# OX05B1S_CAM0.net
KiCad netlist of a schematic drawn in Altium Designer
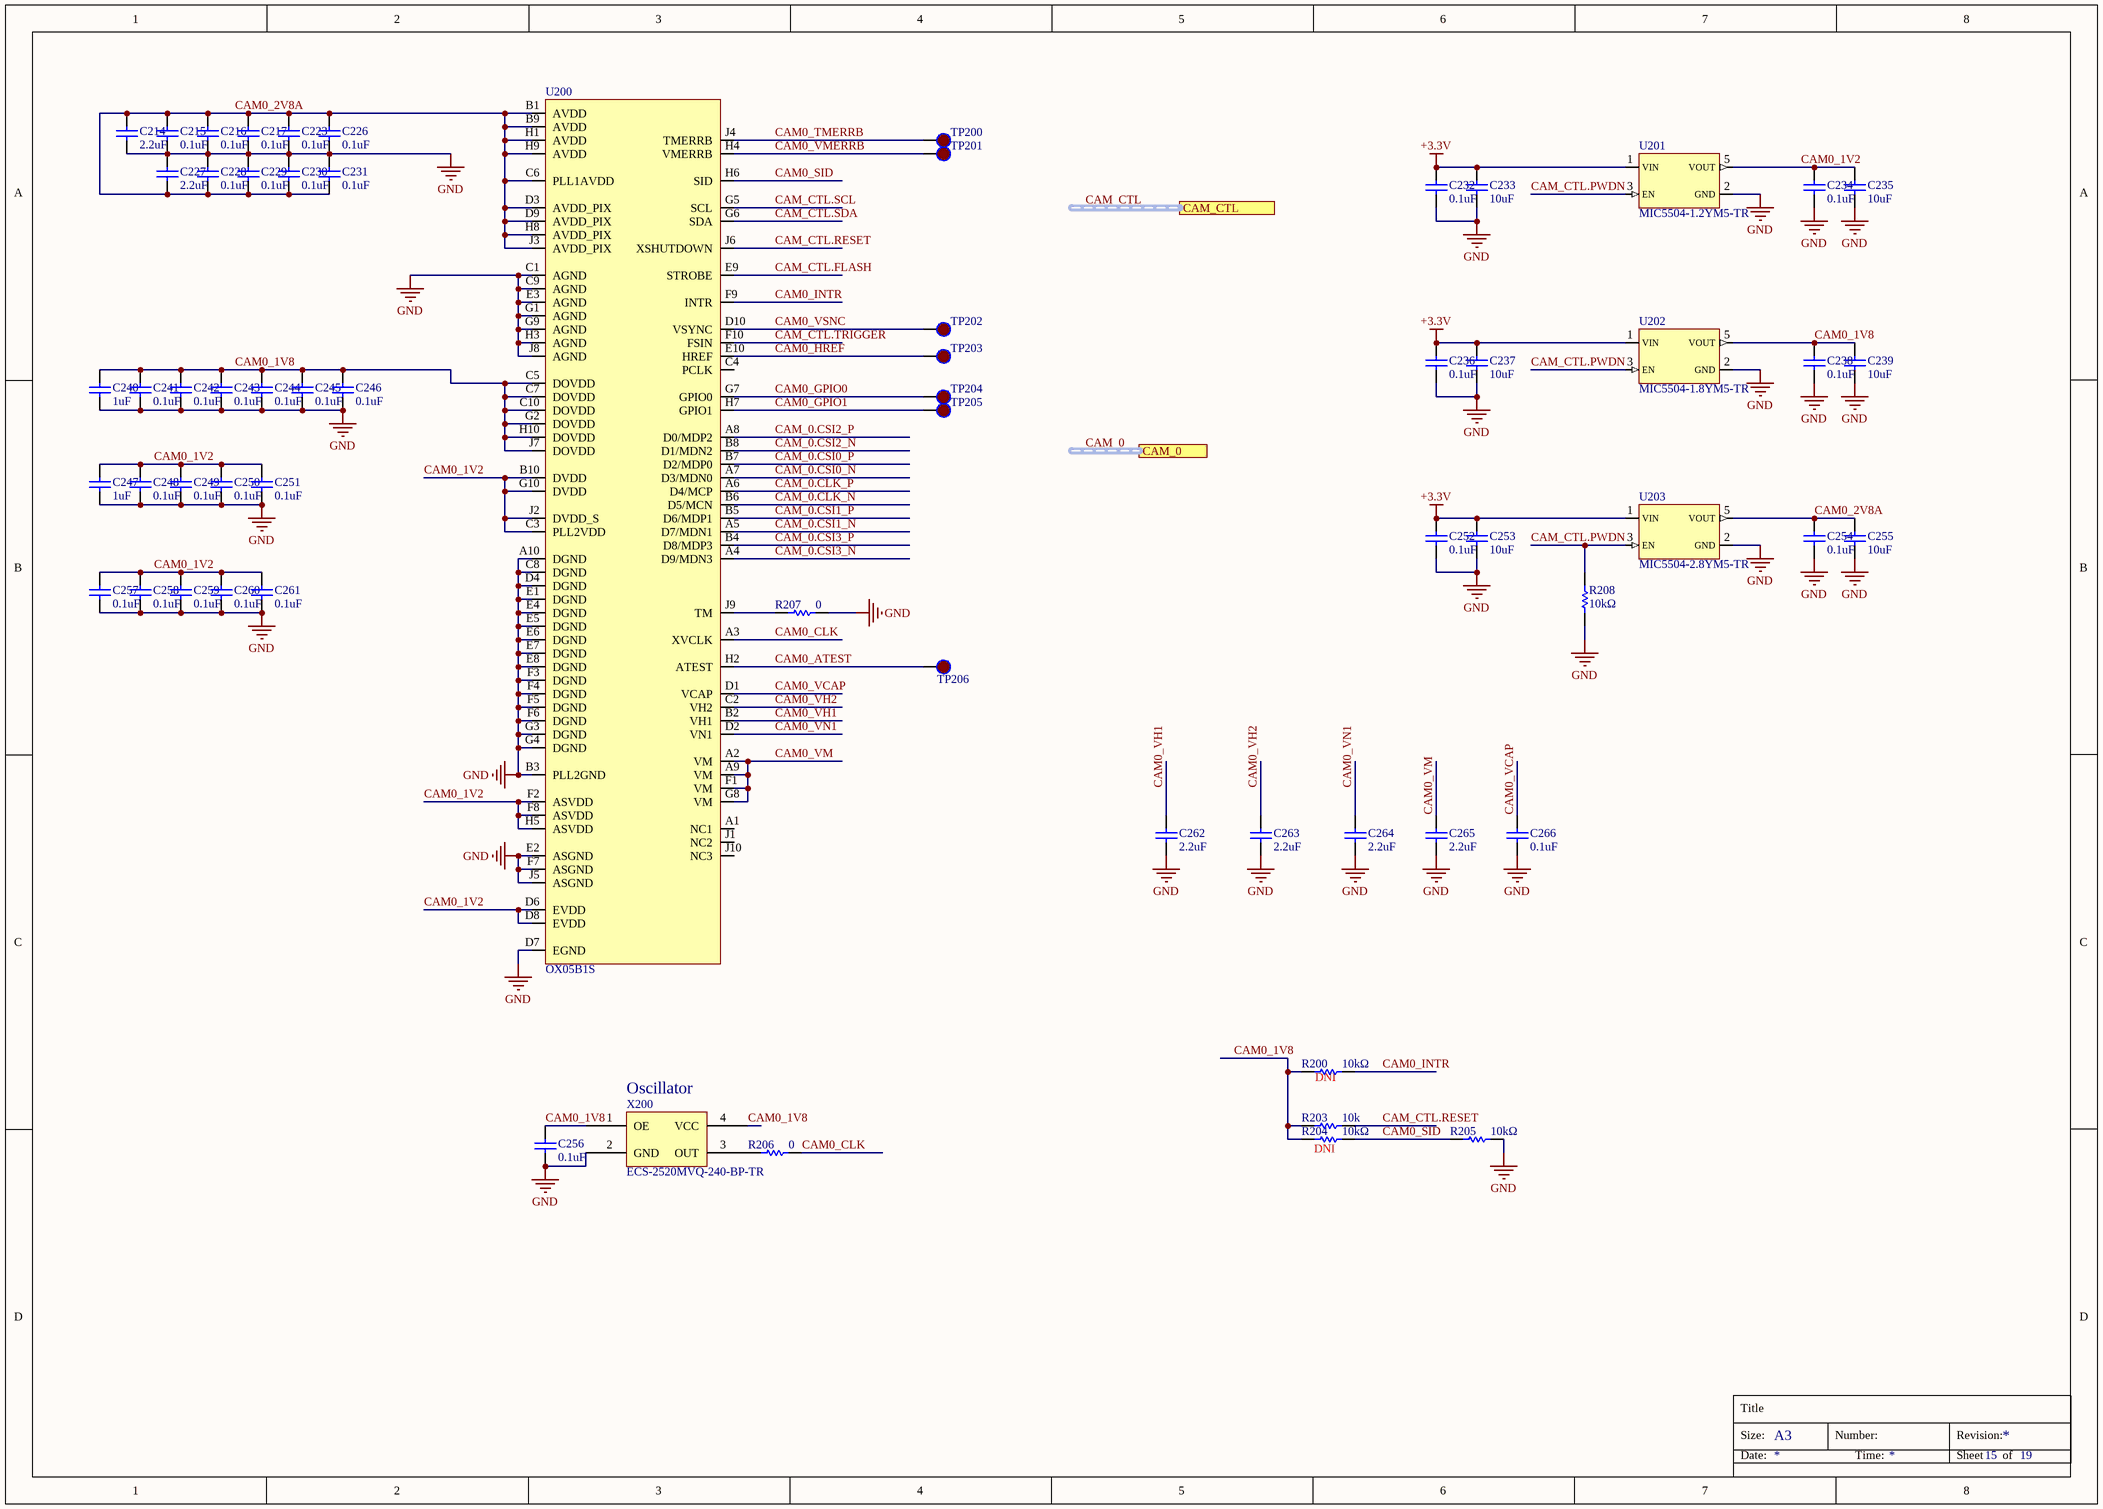
[diagram p0: OX05B1S_CAM0.SchDoc]

(export (version "E")
  (design (tool "Eeschema 10.0.6"))
  (components
    (comp (ref "C214")
      (value "2.2uF")
      (footprint "Signetik-passives:0402_CAP_NP")
      (description "CAP CER 2.2UF 6.3V X5R ±10% 0402")
      (fields
        (field (name "MANUFACTURER") "Murata")
        (field (name "MANUFACTURER PART NUMBER") "GRM155R60J225KE95D")
      )
      (libsource (lib "Signetik-passives") (part "0402C_2.2UF_6.3V_10%_X5R"))
    )
    (comp (ref "C215")
      (value "0.1uF")
      (footprint "signetik-passives:0402_CAP_NP")
      (description "CAP CER 0.1UF 25V X7R 0402")
      (fields (field (name "MANUFACTURER") "AVX") (field (name "MANUFACTURER PART NUMBER") "04023C104KAT2A"))
      (libsource (lib "Signetik-passives") (part "0402C_0.1UF_25V_10%_X7R"))
    )
    (comp (ref "C216")
      (value "0.1uF")
      (footprint "signetik-passives:0402_CAP_NP")
      (description "CAP CER 0.1UF 25V X7R 0402")
      (fields (field (name "MANUFACTURER") "AVX") (field (name "MANUFACTURER PART NUMBER") "04023C104KAT2A"))
      (libsource (lib "Signetik-passives") (part "0402C_0.1UF_25V_10%_X7R"))
    )
    (comp (ref "C217")
      (value "0.1uF")
      (footprint "signetik-passives:0402_CAP_NP")
      (description "CAP CER 0.1UF 25V X7R 0402")
      (fields (field (name "MANUFACTURER") "AVX") (field (name "MANUFACTURER PART NUMBER") "04023C104KAT2A"))
      (libsource (lib "Signetik-passives") (part "0402C_0.1UF_25V_10%_X7R"))
    )
    (comp (ref "C223")
      (value "0.1uF")
      (footprint "signetik-passives:0402_CAP_NP")
      (description "CAP CER 0.1UF 25V X7R 0402")
      (fields (field (name "MANUFACTURER") "AVX") (field (name "MANUFACTURER PART NUMBER") "04023C104KAT2A"))
      (libsource (lib "Signetik-passives") (part "0402C_0.1UF_25V_10%_X7R"))
    )
    (comp (ref "C226")
      (value "0.1uF")
      (footprint "signetik-passives:0402_CAP_NP")
      (description "CAP CER 0.1UF 25V X7R 0402")
      (fields (field (name "MANUFACTURER") "AVX") (field (name "MANUFACTURER PART NUMBER") "04023C104KAT2A"))
      (libsource (lib "Signetik-passives") (part "0402C_0.1UF_25V_10%_X7R"))
    )
    (comp (ref "C227")
      (value "2.2uF")
      (footprint "Signetik-passives:0402_CAP_NP")
      (description "CAP CER 2.2UF 6.3V X5R ±10% 0402")
      (fields
        (field (name "MANUFACTURER") "Murata")
        (field (name "MANUFACTURER PART NUMBER") "GRM155R60J225KE95D")
      )
      (libsource (lib "Signetik-passives") (part "0402C_2.2UF_6.3V_10%_X5R"))
    )
    (comp (ref "C228")
      (value "0.1uF")
      (footprint "signetik-passives:0402_CAP_NP")
      (description "CAP CER 0.1UF 25V X7R 0402")
      (fields (field (name "MANUFACTURER") "AVX") (field (name "MANUFACTURER PART NUMBER") "04023C104KAT2A"))
      (libsource (lib "Signetik-passives") (part "0402C_0.1UF_25V_10%_X7R"))
    )
    (comp (ref "C229")
      (value "0.1uF")
      (footprint "signetik-passives:0402_CAP_NP")
      (description "CAP CER 0.1UF 25V X7R 0402")
      (fields (field (name "MANUFACTURER") "AVX") (field (name "MANUFACTURER PART NUMBER") "04023C104KAT2A"))
      (libsource (lib "Signetik-passives") (part "0402C_0.1UF_25V_10%_X7R"))
    )
    (comp (ref "C230")
      (value "0.1uF")
      (footprint "signetik-passives:0402_CAP_NP")
      (description "CAP CER 0.1UF 25V X7R 0402")
      (fields (field (name "MANUFACTURER") "AVX") (field (name "MANUFACTURER PART NUMBER") "04023C104KAT2A"))
      (libsource (lib "Signetik-passives") (part "0402C_0.1UF_25V_10%_X7R"))
    )
    (comp (ref "C231")
      (value "0.1uF")
      (footprint "signetik-passives:0402_CAP_NP")
      (description "CAP CER 0.1UF 25V X7R 0402")
      (fields (field (name "MANUFACTURER") "AVX") (field (name "MANUFACTURER PART NUMBER") "04023C104KAT2A"))
      (libsource (lib "Signetik-passives") (part "0402C_0.1UF_25V_10%_X7R"))
    )
    (comp (ref "C232")
      (value "0.1uF")
      (footprint "signetik-passives:0402_CAP_NP")
      (description "CAP CER 0.1UF 25V X7R 0402")
      (fields (field (name "MANUFACTURER") "AVX") (field (name "MANUFACTURER PART NUMBER") "04023C104KAT2A"))
      (libsource (lib "Signetik-passives") (part "0402C_0.1UF_25V_10%_X7R"))
    )
    (comp (ref "C233")
      (value "10uF")
      (footprint "signetik-passives:0603_CAP_NP")
      (description "CAP CER 10UF 10V X5R 0603")
      (fields
        (field (name "MANUFACTURER") "Taiyo Yuden")
        (field (name "MANUFACTURER PART NUMBER") "LMK107BBJ106MALT")
      )
      (libsource (lib "Signetik-passives") (part "0603C_10UF_10V_20%_X5R"))
    )
    (comp (ref "C234")
      (value "0.1uF")
      (footprint "signetik-passives:0402_CAP_NP")
      (description "CAP CER 0.1UF 25V X7R 0402")
      (fields (field (name "MANUFACTURER") "AVX") (field (name "MANUFACTURER PART NUMBER") "04023C104KAT2A"))
      (libsource (lib "Signetik-passives") (part "0402C_0.1UF_25V_10%_X7R"))
    )
    (comp (ref "C235")
      (value "10uF")
      (footprint "signetik-passives:0603_CAP_NP")
      (description "CAP CER 10UF 10V X5R 0603")
      (fields
        (field (name "MANUFACTURER") "Taiyo Yuden")
        (field (name "MANUFACTURER PART NUMBER") "LMK107BBJ106MALT")
      )
      (libsource (lib "Signetik-passives") (part "0603C_10UF_10V_20%_X5R"))
    )
    (comp (ref "C236")
      (value "0.1uF")
      (footprint "signetik-passives:0402_CAP_NP")
      (description "CAP CER 0.1UF 25V X7R 0402")
      (fields (field (name "MANUFACTURER") "AVX") (field (name "MANUFACTURER PART NUMBER") "04023C104KAT2A"))
      (libsource (lib "Signetik-passives") (part "0402C_0.1UF_25V_10%_X7R"))
    )
    (comp (ref "C237")
      (value "10uF")
      (footprint "signetik-passives:0603_CAP_NP")
      (description "CAP CER 10UF 10V X5R 0603")
      (fields
        (field (name "MANUFACTURER") "Taiyo Yuden")
        (field (name "MANUFACTURER PART NUMBER") "LMK107BBJ106MALT")
      )
      (libsource (lib "Signetik-passives") (part "0603C_10UF_10V_20%_X5R"))
    )
    (comp (ref "C238")
      (value "0.1uF")
      (footprint "signetik-passives:0402_CAP_NP")
      (description "CAP CER 0.1UF 25V X7R 0402")
      (fields (field (name "MANUFACTURER") "AVX") (field (name "MANUFACTURER PART NUMBER") "04023C104KAT2A"))
      (libsource (lib "Signetik-passives") (part "0402C_0.1UF_25V_10%_X7R"))
    )
    (comp (ref "C239")
      (value "10uF")
      (footprint "signetik-passives:0603_CAP_NP")
      (description "CAP CER 10UF 10V X5R 0603")
      (fields
        (field (name "MANUFACTURER") "Taiyo Yuden")
        (field (name "MANUFACTURER PART NUMBER") "LMK107BBJ106MALT")
      )
      (libsource (lib "Signetik-passives") (part "0603C_10UF_10V_20%_X5R"))
    )
    (comp (ref "C240")
      (value "1uF")
      (footprint "Signetik-passives:0402_CAP_NP")
      (description "CAP CER 1UF 16V X5R 0402 ±10%")
      (fields
        (field (name "MANUFACTURER") "Taiyo Yuden")
        (field (name "MANUFACTURER PART NUMBER") "EMK105BJ105KV-F")
      )
      (libsource (lib "Signetik-passives") (part "0402C_1UF_16V_10%_X5R"))
    )
    (comp (ref "C241")
      (value "0.1uF")
      (footprint "signetik-passives:0402_CAP_NP")
      (description "CAP CER 0.1UF 25V X7R 0402")
      (fields (field (name "MANUFACTURER") "AVX") (field (name "MANUFACTURER PART NUMBER") "04023C104KAT2A"))
      (libsource (lib "Signetik-passives") (part "0402C_0.1UF_25V_10%_X7R"))
    )
    (comp (ref "C242")
      (value "0.1uF")
      (footprint "signetik-passives:0402_CAP_NP")
      (description "CAP CER 0.1UF 25V X7R 0402")
      (fields (field (name "MANUFACTURER") "AVX") (field (name "MANUFACTURER PART NUMBER") "04023C104KAT2A"))
      (libsource (lib "Signetik-passives") (part "0402C_0.1UF_25V_10%_X7R"))
    )
    (comp (ref "C243")
      (value "0.1uF")
      (footprint "signetik-passives:0402_CAP_NP")
      (description "CAP CER 0.1UF 25V X7R 0402")
      (fields (field (name "MANUFACTURER") "AVX") (field (name "MANUFACTURER PART NUMBER") "04023C104KAT2A"))
      (libsource (lib "Signetik-passives") (part "0402C_0.1UF_25V_10%_X7R"))
    )
    (comp (ref "C244")
      (value "0.1uF")
      (footprint "signetik-passives:0402_CAP_NP")
      (description "CAP CER 0.1UF 25V X7R 0402")
      (fields (field (name "MANUFACTURER") "AVX") (field (name "MANUFACTURER PART NUMBER") "04023C104KAT2A"))
      (libsource (lib "Signetik-passives") (part "0402C_0.1UF_25V_10%_X7R"))
    )
    (comp (ref "C245")
      (value "0.1uF")
      (footprint "signetik-passives:0402_CAP_NP")
      (description "CAP CER 0.1UF 25V X7R 0402")
      (fields (field (name "MANUFACTURER") "AVX") (field (name "MANUFACTURER PART NUMBER") "04023C104KAT2A"))
      (libsource (lib "Signetik-passives") (part "0402C_0.1UF_25V_10%_X7R"))
    )
    (comp (ref "C246")
      (value "0.1uF")
      (footprint "signetik-passives:0402_CAP_NP")
      (description "CAP CER 0.1UF 25V X7R 0402")
      (fields (field (name "MANUFACTURER") "AVX") (field (name "MANUFACTURER PART NUMBER") "04023C104KAT2A"))
      (libsource (lib "Signetik-passives") (part "0402C_0.1UF_25V_10%_X7R"))
    )
    (comp (ref "C247")
      (value "1uF")
      (footprint "Signetik-passives:0402_CAP_NP")
      (description "CAP CER 1UF 16V X5R 0402 ±10%")
      (fields
        (field (name "MANUFACTURER") "Taiyo Yuden")
        (field (name "MANUFACTURER PART NUMBER") "EMK105BJ105KV-F")
      )
      (libsource (lib "Signetik-passives") (part "0402C_1UF_16V_10%_X5R"))
    )
    (comp (ref "C248")
      (value "0.1uF")
      (footprint "signetik-passives:0402_CAP_NP")
      (description "CAP CER 0.1UF 25V X7R 0402")
      (fields (field (name "MANUFACTURER") "AVX") (field (name "MANUFACTURER PART NUMBER") "04023C104KAT2A"))
      (libsource (lib "Signetik-passives") (part "0402C_0.1UF_25V_10%_X7R"))
    )
    (comp (ref "C249")
      (value "0.1uF")
      (footprint "signetik-passives:0402_CAP_NP")
      (description "CAP CER 0.1UF 25V X7R 0402")
      (fields (field (name "MANUFACTURER") "AVX") (field (name "MANUFACTURER PART NUMBER") "04023C104KAT2A"))
      (libsource (lib "Signetik-passives") (part "0402C_0.1UF_25V_10%_X7R"))
    )
    (comp (ref "C250")
      (value "0.1uF")
      (footprint "signetik-passives:0402_CAP_NP")
      (description "CAP CER 0.1UF 25V X7R 0402")
      (fields (field (name "MANUFACTURER") "AVX") (field (name "MANUFACTURER PART NUMBER") "04023C104KAT2A"))
      (libsource (lib "Signetik-passives") (part "0402C_0.1UF_25V_10%_X7R"))
    )
    (comp (ref "C251")
      (value "0.1uF")
      (footprint "signetik-passives:0402_CAP_NP")
      (description "CAP CER 0.1UF 25V X7R 0402")
      (fields (field (name "MANUFACTURER") "AVX") (field (name "MANUFACTURER PART NUMBER") "04023C104KAT2A"))
      (libsource (lib "Signetik-passives") (part "0402C_0.1UF_25V_10%_X7R"))
    )
    (comp (ref "C252")
      (value "0.1uF")
      (footprint "signetik-passives:0402_CAP_NP")
      (description "CAP CER 0.1UF 25V X7R 0402")
      (fields (field (name "MANUFACTURER") "AVX") (field (name "MANUFACTURER PART NUMBER") "04023C104KAT2A"))
      (libsource (lib "Signetik-passives") (part "0402C_0.1UF_25V_10%_X7R"))
    )
    (comp (ref "C253")
      (value "10uF")
      (footprint "signetik-passives:0603_CAP_NP")
      (description "CAP CER 10UF 10V X5R 0603")
      (fields
        (field (name "MANUFACTURER") "Taiyo Yuden")
        (field (name "MANUFACTURER PART NUMBER") "LMK107BBJ106MALT")
      )
      (libsource (lib "Signetik-passives") (part "0603C_10UF_10V_20%_X5R"))
    )
    (comp (ref "C254")
      (value "0.1uF")
      (footprint "signetik-passives:0402_CAP_NP")
      (description "CAP CER 0.1UF 25V X7R 0402")
      (fields (field (name "MANUFACTURER") "AVX") (field (name "MANUFACTURER PART NUMBER") "04023C104KAT2A"))
      (libsource (lib "Signetik-passives") (part "0402C_0.1UF_25V_10%_X7R"))
    )
    (comp (ref "C255")
      (value "10uF")
      (footprint "signetik-passives:0603_CAP_NP")
      (description "CAP CER 10UF 10V X5R 0603")
      (fields
        (field (name "MANUFACTURER") "Taiyo Yuden")
        (field (name "MANUFACTURER PART NUMBER") "LMK107BBJ106MALT")
      )
      (libsource (lib "Signetik-passives") (part "0603C_10UF_10V_20%_X5R"))
    )
    (comp (ref "C256")
      (value "0.1uF")
      (footprint "signetik-passives:0402_CAP_NP")
      (description "CAP CER 0.1UF 25V X7R 0402")
      (fields (field (name "MANUFACTURER") "AVX") (field (name "MANUFACTURER PART NUMBER") "04023C104KAT2A"))
      (libsource (lib "Signetik-passives") (part "0402C_0.1UF_25V_10%_X7R"))
    )
    (comp (ref "C257")
      (value "0.1uF")
      (footprint "signetik-passives:0402_CAP_NP")
      (description "CAP CER 0.1UF 25V X7R 0402")
      (fields (field (name "MANUFACTURER") "AVX") (field (name "MANUFACTURER PART NUMBER") "04023C104KAT2A"))
      (libsource (lib "Signetik-passives") (part "0402C_0.1UF_25V_10%_X7R"))
    )
    (comp (ref "C258")
      (value "0.1uF")
      (footprint "signetik-passives:0402_CAP_NP")
      (description "CAP CER 0.1UF 25V X7R 0402")
      (fields (field (name "MANUFACTURER") "AVX") (field (name "MANUFACTURER PART NUMBER") "04023C104KAT2A"))
      (libsource (lib "Signetik-passives") (part "0402C_0.1UF_25V_10%_X7R"))
    )
    (comp (ref "C259")
      (value "0.1uF")
      (footprint "signetik-passives:0402_CAP_NP")
      (description "CAP CER 0.1UF 25V X7R 0402")
      (fields (field (name "MANUFACTURER") "AVX") (field (name "MANUFACTURER PART NUMBER") "04023C104KAT2A"))
      (libsource (lib "Signetik-passives") (part "0402C_0.1UF_25V_10%_X7R"))
    )
    (comp (ref "C260")
      (value "0.1uF")
      (footprint "signetik-passives:0402_CAP_NP")
      (description "CAP CER 0.1UF 25V X7R 0402")
      (fields (field (name "MANUFACTURER") "AVX") (field (name "MANUFACTURER PART NUMBER") "04023C104KAT2A"))
      (libsource (lib "Signetik-passives") (part "0402C_0.1UF_25V_10%_X7R"))
    )
    (comp (ref "C261")
      (value "0.1uF")
      (footprint "signetik-passives:0402_CAP_NP")
      (description "CAP CER 0.1UF 25V X7R 0402")
      (fields (field (name "MANUFACTURER") "AVX") (field (name "MANUFACTURER PART NUMBER") "04023C104KAT2A"))
      (libsource (lib "Signetik-passives") (part "0402C_0.1UF_25V_10%_X7R"))
    )
    (comp (ref "C262")
      (value "2.2uF")
      (footprint "Signetik-passives:0402_CAP_NP")
      (description "CAP CER 2.2UF 6.3V X5R ±10% 0402")
      (fields
        (field (name "MANUFACTURER") "Murata")
        (field (name "MANUFACTURER PART NUMBER") "GRM155R60J225KE95D")
      )
      (libsource (lib "Signetik-passives") (part "0402C_2.2UF_6.3V_10%_X5R"))
    )
    (comp (ref "C263")
      (value "2.2uF")
      (footprint "Signetik-passives:0402_CAP_NP")
      (description "CAP CER 2.2UF 6.3V X5R ±10% 0402")
      (fields
        (field (name "MANUFACTURER") "Murata")
        (field (name "MANUFACTURER PART NUMBER") "GRM155R60J225KE95D")
      )
      (libsource (lib "Signetik-passives") (part "0402C_2.2UF_6.3V_10%_X5R"))
    )
    (comp (ref "C264")
      (value "2.2uF")
      (footprint "Signetik-passives:0402_CAP_NP")
      (description "CAP CER 2.2UF 6.3V X5R ±10% 0402")
      (fields
        (field (name "MANUFACTURER") "Murata")
        (field (name "MANUFACTURER PART NUMBER") "GRM155R60J225KE95D")
      )
      (libsource (lib "Signetik-passives") (part "0402C_2.2UF_6.3V_10%_X5R"))
    )
    (comp (ref "C265")
      (value "2.2uF")
      (footprint "Signetik-passives:0402_CAP_NP")
      (description "CAP CER 2.2UF 6.3V X5R ±10% 0402")
      (fields
        (field (name "MANUFACTURER") "Murata")
        (field (name "MANUFACTURER PART NUMBER") "GRM155R60J225KE95D")
      )
      (libsource (lib "Signetik-passives") (part "0402C_2.2UF_6.3V_10%_X5R"))
    )
    (comp (ref "C266")
      (value "0.1uF")
      (footprint "signetik-passives:0402_CAP_NP")
      (description "CAP CER 0.1UF 25V X7R 0402")
      (fields (field (name "MANUFACTURER") "AVX") (field (name "MANUFACTURER PART NUMBER") "04023C104KAT2A"))
      (libsource (lib "Signetik-passives") (part "0402C_0.1UF_25V_10%_X7R"))
    )
    (comp (ref "R200")
      (value "10kΩ")
      (footprint "signetik-passives:0603_RES")
      (description "RES SMD 10K OHM 1% 1/10W 0603")
      (fields
        (field (name "MANUFACTURER") "Yageo")
        (field (name "MANUFACTURER PART NUMBER") "RC0603FR-0710KL")
        (field (name "POPULATE") "DNI")
      )
      (libsource (lib "Signetik-passives") (part "0603R_10k_1%_0.1W"))
    )
    (comp (ref "R203")
      (value "10k")
      (footprint "0402_RES")
      (description "RES SMD 10K OHM 1% 1/16W 0402")
      (fields
        (field (name "MANUFACTURER") "Yageo")
        (field (name "MANUFACTURER PART NUMBER") "RC0402FR-0710KL")
      )
      (libsource (lib "Signetik-passives") (part "0402R_10k_1%_0.063W"))
    )
    (comp (ref "R204")
      (value "10kΩ")
      (footprint "signetik-passives:0603_RES")
      (description "RES SMD 10K OHM 1% 1/10W 0603")
      (fields
        (field (name "MANUFACTURER") "Yageo")
        (field (name "MANUFACTURER PART NUMBER") "RC0603FR-0710KL")
        (field (name "POPULATE") "DNI")
      )
      (libsource (lib "Signetik-passives") (part "0603R_10k_1%_0.1W"))
    )
    (comp (ref "R205")
      (value "10kΩ")
      (footprint "signetik-passives:0603_RES")
      (description "RES SMD 10K OHM 1% 1/10W 0603")
      (fields
        (field (name "MANUFACTURER") "Yageo")
        (field (name "MANUFACTURER PART NUMBER") "RC0603FR-0710KL")
      )
      (libsource (lib "Signetik-passives") (part "0603R_10k_1%_0.1W"))
    )
    (comp (ref "R206")
      (value "0")
      (footprint "signetik-passives:0603_RES")
      (description "Resistor 0 ohm 0.1W 0603")
      (fields (field (name "MFG") "Yageo") (field (name "MPN") "RC0603JR-070RL"))
      (libsource (lib "Signetik-passives") (part "0603R_0_0.1W"))
    )
    (comp (ref "R207")
      (value "0")
      (footprint "signetik-passives:0603_RES")
      (description "Resistor 0 ohm 0.1W 0603")
      (fields
        (field (name "MANUFACTURER") "Yageo")
        (field (name "MANUFACTURER PART NUMBER") "RC0603JR-070RL")
      )
      (libsource (lib "Signetik-passives") (part "0603R_0_0.1W"))
    )
    (comp (ref "R208")
      (value "10kΩ")
      (footprint "signetik-passives:0603_RES")
      (description "RES SMD 10K OHM 1% 1/10W 0603")
      (fields
        (field (name "MANUFACTURER") "Yageo")
        (field (name "MANUFACTURER PART NUMBER") "RC0603FR-0710KL")
      )
      (libsource (lib "Signetik-passives") (part "0603R_10k_1%_0.1W"))
    )
    (comp (ref "TP200")
      (value "TestPoint_1mm_SM")
      (footprint "TESTPAD_1mm")
      (libsource (lib "Signetik-TP_Mech_Others") (part "TestPoint_1mm_SM"))
    )
    (comp (ref "TP201")
      (value "TestPoint_1mm_SM")
      (footprint "TESTPAD_1mm")
      (libsource (lib "Signetik-TP_Mech_Others") (part "TestPoint_1mm_SM"))
    )
    (comp (ref "TP202")
      (value "TestPoint_1mm_SM")
      (footprint "TESTPAD_1mm")
      (libsource (lib "Signetik-TP_Mech_Others") (part "TestPoint_1mm_SM"))
    )
    (comp (ref "TP203")
      (value "TestPoint_1mm_SM")
      (footprint "TESTPAD_1mm")
      (libsource (lib "Signetik-TP_Mech_Others") (part "TestPoint_1mm_SM"))
    )
    (comp (ref "TP204")
      (value "TestPoint_1mm_SM")
      (footprint "TESTPAD_1mm")
      (libsource (lib "Signetik-TP_Mech_Others") (part "TestPoint_1mm_SM"))
    )
    (comp (ref "TP205")
      (value "TestPoint_1mm_SM")
      (footprint "TESTPAD_1mm")
      (libsource (lib "Signetik-TP_Mech_Others") (part "TestPoint_1mm_SM"))
    )
    (comp (ref "TP206")
      (value "TestPoint_1mm_SM")
      (footprint "TESTPIN_1mm")
      (libsource (lib "Signetik-TP_Mech_Others") (part "TestPoint_1mm_SM"))
    )
    (comp (ref "U200")
      (value "OX05B1S")
      (footprint "BGA_OX05B1S")
      (description "1/2.53\" CMOS 5MP image sensor")
      (fields (field (name "MANUFACTURER") "OMNIVISION"))
      (libsource (lib "OX05B1S Module") (part "OX05B1S"))
    )
    (comp (ref "U201")
      (value "MIC5504-1.2YM5-TR")
      (footprint "SOT23-5")
      (description "IC REG LINEAR 1.2V 300MA SOT23-5")
      (fields (field (name "MANUFACTURER") "Microchip"))
      (libsource (lib "cvlib") (part "MIC550x"))
    )
    (comp (ref "U202")
      (value "MIC5504-1.8YM5-TR")
      (footprint "SOT23-5")
      (description "Linear Voltage Regulator IC Positive Fixed 1 Output 1.8V 300mA SOT-23-5")
      (fields (field (name "MANUFACTURER") "Microchip"))
      (libsource (lib "cvlib") (part "MIC550x"))
    )
    (comp (ref "U203")
      (value "MIC5504-2.8YM5-TR")
      (footprint "SOT23-5")
      (description "LDO Fixed Output Voltage Regulator MIC5504-2.8YM5-TR, 2.8V, 300mA, SOT23-5 /tape-3k/")
      (fields (field (name "MANUFACTURER") "Microchip"))
      (libsource (lib "cvlib") (part "MIC550x"))
    )
    (comp (ref "X200")
      (value "ECS-2520MVQ-240-BP-TR")
      (footprint "Active Oscillator 2520")
      (description "Oscillator XO 24MHz ±50ppm 15pF HCMOS 55% 1.8V/2.5V/3.3V Automotive 4-Pin Mini-CSMD T/R")
      (fields (field (name "MANUFACTURER") "ECS International"))
      (libsource (lib "Crystal_and_oscillator") (part "Oscillator_2520"))
    )
  )
  (nets
    (net (code "3") (name "+3.3V") (class "Default")
      (node (ref "C232") (pin "2") (pinfunction "2_2") (pintype "passive"))
      (node (ref "C233") (pin "2") (pinfunction "2_2") (pintype "passive"))
      (node (ref "C236") (pin "2") (pinfunction "2_2") (pintype "passive"))
      (node (ref "C237") (pin "2") (pinfunction "2_2") (pintype "passive"))
      (node (ref "C252") (pin "2") (pinfunction "2_2") (pintype "passive"))
      (node (ref "C253") (pin "2") (pinfunction "2_2") (pintype "passive"))
      (node (ref "U201") (pin "1") (pinfunction "VIN_1") (pintype "power_in"))
      (node (ref "U202") (pin "1") (pinfunction "VIN_1") (pintype "power_in"))
      (node (ref "U203") (pin "1") (pinfunction "VIN_1") (pintype "power_in"))
    )
    (net (code "4") (name "/CAM0_1V2") (class "Default")
      (node (ref "C234") (pin "2") (pinfunction "2_2") (pintype "passive"))
      (node (ref "C235") (pin "2") (pinfunction "2_2") (pintype "passive"))
      (node (ref "C247") (pin "2") (pinfunction "2_2") (pintype "passive"))
      (node (ref "C248") (pin "2") (pinfunction "2_2") (pintype "passive"))
      (node (ref "C249") (pin "2") (pinfunction "2_2") (pintype "passive"))
      (node (ref "C250") (pin "2") (pinfunction "2_2") (pintype "passive"))
      (node (ref "C251") (pin "2") (pinfunction "2_2") (pintype "passive"))
      (node (ref "C257") (pin "2") (pinfunction "2_2") (pintype "passive"))
      (node (ref "C258") (pin "2") (pinfunction "2_2") (pintype "passive"))
      (node (ref "C259") (pin "2") (pinfunction "2_2") (pintype "passive"))
      (node (ref "C260") (pin "2") (pinfunction "2_2") (pintype "passive"))
      (node (ref "C261") (pin "2") (pinfunction "2_2") (pintype "passive"))
      (node (ref "U200") (pin "B10") (pinfunction "DVDD_B10") (pintype "passive"))
      (node (ref "U200") (pin "C3") (pinfunction "PLL2VDD_C3") (pintype "passive"))
      (node (ref "U200") (pin "D6") (pinfunction "EVDD_D6") (pintype "passive"))
      (node (ref "U200") (pin "D8") (pinfunction "EVDD_D8") (pintype "passive"))
      (node (ref "U200") (pin "F2") (pinfunction "ASVDD_F2") (pintype "passive"))
      (node (ref "U200") (pin "F8") (pinfunction "ASVDD_F8") (pintype "passive"))
      (node (ref "U200") (pin "G10") (pinfunction "DVDD_G10") (pintype "passive"))
      (node (ref "U200") (pin "H5") (pinfunction "ASVDD_H5") (pintype "passive"))
      (node (ref "U200") (pin "J2") (pinfunction "DVDD_S_J2") (pintype "passive"))
      (node (ref "U201") (pin "5") (pinfunction "VOUT_5") (pintype "output"))
    )
    (net (code "5") (name "/CAM0_1V8") (class "Default")
      (node (ref "C238") (pin "2") (pinfunction "2_2") (pintype "passive"))
      (node (ref "C239") (pin "2") (pinfunction "2_2") (pintype "passive"))
      (node (ref "C240") (pin "2") (pinfunction "2_2") (pintype "passive"))
      (node (ref "C241") (pin "2") (pinfunction "2_2") (pintype "passive"))
      (node (ref "C242") (pin "2") (pinfunction "2_2") (pintype "passive"))
      (node (ref "C243") (pin "2") (pinfunction "2_2") (pintype "passive"))
      (node (ref "C244") (pin "2") (pinfunction "2_2") (pintype "passive"))
      (node (ref "C245") (pin "2") (pinfunction "2_2") (pintype "passive"))
      (node (ref "C246") (pin "2") (pinfunction "2_2") (pintype "passive"))
      (node (ref "C256") (pin "2") (pinfunction "2_2") (pintype "passive"))
      (node (ref "R200") (pin "2") (pinfunction "2_2") (pintype "passive"))
      (node (ref "R203") (pin "2") (pinfunction "2_2") (pintype "passive"))
      (node (ref "R204") (pin "2") (pinfunction "2_2") (pintype "passive"))
      (node (ref "U200") (pin "C10") (pinfunction "DOVDD_C10") (pintype "passive"))
      (node (ref "U200") (pin "C5") (pinfunction "DOVDD_C5") (pintype "passive"))
      (node (ref "U200") (pin "C7") (pinfunction "DOVDD_C7") (pintype "passive"))
      (node (ref "U200") (pin "G2") (pinfunction "DOVDD_G2") (pintype "passive"))
      (node (ref "U200") (pin "H10") (pinfunction "DOVDD_H10") (pintype "passive"))
      (node (ref "U200") (pin "J7") (pinfunction "DOVDD_J7") (pintype "passive"))
      (node (ref "U202") (pin "5") (pinfunction "VOUT_5") (pintype "output"))
      (node (ref "X200") (pin "1") (pinfunction "OE_1") (pintype "passive"))
      (node (ref "X200") (pin "4") (pinfunction "VCC_4") (pintype "passive"))
    )
    (net (code "6") (name "/CAM0_2V8A") (class "Default")
      (node (ref "C214") (pin "2") (pinfunction "2_2") (pintype "passive"))
      (node (ref "C215") (pin "2") (pinfunction "2_2") (pintype "passive"))
      (node (ref "C216") (pin "2") (pinfunction "2_2") (pintype "passive"))
      (node (ref "C217") (pin "2") (pinfunction "2_2") (pintype "passive"))
      (node (ref "C223") (pin "2") (pinfunction "2_2") (pintype "passive"))
      (node (ref "C226") (pin "2") (pinfunction "2_2") (pintype "passive"))
      (node (ref "C227") (pin "1") (pinfunction "1_1") (pintype "passive"))
      (node (ref "C228") (pin "1") (pinfunction "1_1") (pintype "passive"))
      (node (ref "C229") (pin "1") (pinfunction "1_1") (pintype "passive"))
      (node (ref "C230") (pin "1") (pinfunction "1_1") (pintype "passive"))
      (node (ref "C231") (pin "1") (pinfunction "1_1") (pintype "passive"))
      (node (ref "C254") (pin "2") (pinfunction "2_2") (pintype "passive"))
      (node (ref "C255") (pin "2") (pinfunction "2_2") (pintype "passive"))
      (node (ref "U200") (pin "B1") (pinfunction "AVDD_B1") (pintype "passive"))
      (node (ref "U200") (pin "B9") (pinfunction "AVDD_B9") (pintype "passive"))
      (node (ref "U200") (pin "C6") (pinfunction "PLL1AVDD_C6") (pintype "passive"))
      (node (ref "U200") (pin "D3") (pinfunction "AVDD_PIX_D3") (pintype "passive"))
      (node (ref "U200") (pin "D9") (pinfunction "AVDD_PIX_D9") (pintype "passive"))
      (node (ref "U200") (pin "H1") (pinfunction "AVDD_H1") (pintype "passive"))
      (node (ref "U200") (pin "H8") (pinfunction "AVDD_PIX_H8") (pintype "passive"))
      (node (ref "U200") (pin "H9") (pinfunction "AVDD_H9") (pintype "passive"))
      (node (ref "U200") (pin "J3") (pinfunction "AVDD_PIX_J3") (pintype "passive"))
      (node (ref "U203") (pin "5") (pinfunction "VOUT_5") (pintype "output"))
    )
    (net (code "7") (name "/CAM0_ATEST") (class "Default")
      (node (ref "TP206") (pin "1") (pinfunction "1_1") (pintype "passive"))
      (node (ref "U200") (pin "H2") (pinfunction "ATEST_H2") (pintype "passive"))
    )
    (net (code "8") (name "/CAM0_CLK") (class "Default")
      (node (ref "R206") (pin "2") (pinfunction "2_2") (pintype "passive"))
      (node (ref "U200") (pin "A3") (pinfunction "XVCLK_A3") (pintype "passive"))
    )
    (net (code "9") (name "/CAM0_GPIO0") (class "Default")
      (node (ref "TP204") (pin "1") (pinfunction "1_1") (pintype "passive"))
      (node (ref "U200") (pin "G7") (pinfunction "GPIO0_G7") (pintype "passive"))
    )
    (net (code "10") (name "/CAM0_GPIO1") (class "Default")
      (node (ref "TP205") (pin "1") (pinfunction "1_1") (pintype "passive"))
      (node (ref "U200") (pin "H7") (pinfunction "GPIO1_H7") (pintype "passive"))
    )
    (net (code "11") (name "/CAM0_HREF") (class "Default")
      (node (ref "TP203") (pin "1") (pinfunction "1_1") (pintype "passive"))
      (node (ref "U200") (pin "E10") (pinfunction "HREF_E10") (pintype "passive"))
    )
    (net (code "12") (name "/CAM0_INTR") (class "Default")
      (node (ref "R200") (pin "1") (pinfunction "1_1") (pintype "passive"))
      (node (ref "U200") (pin "F9") (pinfunction "INTR_F9") (pintype "passive"))
    )
    (net (code "13") (name "/CAM0_SID") (class "Default")
      (node (ref "R204") (pin "1") (pinfunction "1_1") (pintype "passive"))
      (node (ref "R205") (pin "2") (pinfunction "2_2") (pintype "passive"))
      (node (ref "U200") (pin "H6") (pinfunction "SID_H6") (pintype "passive"))
    )
    (net (code "14") (name "/CAM0_TMERRB") (class "Default")
      (node (ref "TP200") (pin "1") (pinfunction "1_1") (pintype "passive"))
      (node (ref "U200") (pin "J4") (pinfunction "TMERRB_J4") (pintype "passive"))
    )
    (net (code "15") (name "/CAM0_VCAP") (class "Default")
      (node (ref "C266") (pin "2") (pinfunction "2_2") (pintype "passive"))
      (node (ref "U200") (pin "D1") (pinfunction "VCAP_D1") (pintype "passive"))
    )
    (net (code "16") (name "/CAM0_VH1") (class "Default")
      (node (ref "C262") (pin "2") (pinfunction "2_2") (pintype "passive"))
      (node (ref "U200") (pin "B2") (pinfunction "VH1_B2") (pintype "passive"))
    )
    (net (code "17") (name "/CAM0_VH2") (class "Default")
      (node (ref "C263") (pin "2") (pinfunction "2_2") (pintype "passive"))
      (node (ref "U200") (pin "C2") (pinfunction "VH2_C2") (pintype "passive"))
    )
    (net (code "18") (name "/CAM0_VM") (class "Default")
      (node (ref "C265") (pin "2") (pinfunction "2_2") (pintype "passive"))
      (node (ref "U200") (pin "A2") (pinfunction "VM_A2") (pintype "passive"))
      (node (ref "U200") (pin "A9") (pinfunction "VM_A9") (pintype "passive"))
      (node (ref "U200") (pin "F1") (pinfunction "VM_F1") (pintype "passive"))
      (node (ref "U200") (pin "G8") (pinfunction "VM_G8") (pintype "passive"))
    )
    (net (code "19") (name "/CAM0_VMERRB") (class "Default")
      (node (ref "TP201") (pin "1") (pinfunction "1_1") (pintype "passive"))
      (node (ref "U200") (pin "H4") (pinfunction "VMERRB_H4") (pintype "passive"))
    )
    (net (code "20") (name "/CAM0_VN1") (class "Default")
      (node (ref "C264") (pin "2") (pinfunction "2_2") (pintype "passive"))
      (node (ref "U200") (pin "D2") (pinfunction "VN1_D2") (pintype "passive"))
    )
    (net (code "21") (name "/CAM0_VSNC") (class "Default")
      (node (ref "TP202") (pin "1") (pinfunction "1_1") (pintype "passive"))
      (node (ref "U200") (pin "D10") (pinfunction "VSYNC_D10") (pintype "passive"))
    )
    (net (code "22") (name "/CAM_0.CLK_N") (class "Default")
      (node (ref "U200") (pin "B6") (pinfunction "D5/MCN_B6") (pintype "passive"))
    )
    (net (code "23") (name "/CAM_0.CLK_P") (class "Default")
      (node (ref "U200") (pin "A6") (pinfunction "D4/MCP_A6") (pintype "passive"))
    )
    (net (code "24") (name "/CAM_0.CSI0_N") (class "Default")
      (node (ref "U200") (pin "A7") (pinfunction "D3/MDN0_A7") (pintype "passive"))
    )
    (net (code "25") (name "/CAM_0.CSI0_P") (class "Default")
      (node (ref "U200") (pin "B7") (pinfunction "D2/MDP0_B7") (pintype "passive"))
    )
    (net (code "26") (name "/CAM_0.CSI1_N") (class "Default")
      (node (ref "U200") (pin "A5") (pinfunction "D7/MDN1_A5") (pintype "passive"))
    )
    (net (code "27") (name "/CAM_0.CSI1_P") (class "Default")
      (node (ref "U200") (pin "B5") (pinfunction "D6/MDP1_B5") (pintype "passive"))
    )
    (net (code "28") (name "/CAM_0.CSI2_N") (class "Default")
      (node (ref "U200") (pin "B8") (pinfunction "D1/MDN2_B8") (pintype "passive"))
    )
    (net (code "29") (name "/CAM_0.CSI2_P") (class "Default")
      (node (ref "U200") (pin "A8") (pinfunction "D0/MDP2_A8") (pintype "passive"))
    )
    (net (code "30") (name "/CAM_0.CSI3_N") (class "Default")
      (node (ref "U200") (pin "A4") (pinfunction "D9/MDN3_A4") (pintype "passive"))
    )
    (net (code "31") (name "/CAM_0.CSI3_P") (class "Default")
      (node (ref "U200") (pin "B4") (pinfunction "D8/MDP3_B4") (pintype "passive"))
    )
    (net (code "32") (name "/CAM_CTL.FLASH") (class "Default")
      (node (ref "U200") (pin "E9") (pinfunction "STROBE_E9") (pintype "passive"))
    )
    (net (code "33") (name "/CAM_CTL.PWDN") (class "Default")
      (node (ref "R208") (pin "1") (pinfunction "1_1") (pintype "passive"))
      (node (ref "U201") (pin "3") (pinfunction "EN_3") (pintype "input"))
      (node (ref "U202") (pin "3") (pinfunction "EN_3") (pintype "input"))
      (node (ref "U203") (pin "3") (pinfunction "EN_3") (pintype "input"))
    )
    (net (code "34") (name "/CAM_CTL.RESET") (class "Default")
      (node (ref "R203") (pin "1") (pinfunction "1_1") (pintype "passive"))
      (node (ref "U200") (pin "J6") (pinfunction "XSHUTDOWN_J6") (pintype "passive"))
    )
    (net (code "35") (name "/CAM_CTL.SCL") (class "Default")
      (node (ref "U200") (pin "G5") (pinfunction "SCL_G5") (pintype "passive"))
    )
    (net (code "36") (name "/CAM_CTL.SDA") (class "Default")
      (node (ref "U200") (pin "G6") (pinfunction "SDA_G6") (pintype "passive"))
    )
    (net (code "37") (name "/CAM_CTL.TRIGGER") (class "Default")
      (node (ref "U200") (pin "F10") (pinfunction "FSIN_F10") (pintype "passive"))
    )
    (net (code "40") (name "GND") (class "Default")
      (node (ref "C214") (pin "1") (pinfunction "1_1") (pintype "passive"))
      (node (ref "C215") (pin "1") (pinfunction "1_1") (pintype "passive"))
      (node (ref "C216") (pin "1") (pinfunction "1_1") (pintype "passive"))
      (node (ref "C217") (pin "1") (pinfunction "1_1") (pintype "passive"))
      (node (ref "C223") (pin "1") (pinfunction "1_1") (pintype "passive"))
      (node (ref "C226") (pin "1") (pinfunction "1_1") (pintype "passive"))
      (node (ref "C227") (pin "2") (pinfunction "2_2") (pintype "passive"))
      (node (ref "C228") (pin "2") (pinfunction "2_2") (pintype "passive"))
      (node (ref "C229") (pin "2") (pinfunction "2_2") (pintype "passive"))
      (node (ref "C230") (pin "2") (pinfunction "2_2") (pintype "passive"))
      (node (ref "C231") (pin "2") (pinfunction "2_2") (pintype "passive"))
      (node (ref "C232") (pin "1") (pinfunction "1_1") (pintype "passive"))
      (node (ref "C233") (pin "1") (pinfunction "1_1") (pintype "passive"))
      (node (ref "C234") (pin "1") (pinfunction "1_1") (pintype "passive"))
      (node (ref "C235") (pin "1") (pinfunction "1_1") (pintype "passive"))
      (node (ref "C236") (pin "1") (pinfunction "1_1") (pintype "passive"))
      (node (ref "C237") (pin "1") (pinfunction "1_1") (pintype "passive"))
      (node (ref "C238") (pin "1") (pinfunction "1_1") (pintype "passive"))
      (node (ref "C239") (pin "1") (pinfunction "1_1") (pintype "passive"))
      (node (ref "C240") (pin "1") (pinfunction "1_1") (pintype "passive"))
      (node (ref "C241") (pin "1") (pinfunction "1_1") (pintype "passive"))
      (node (ref "C242") (pin "1") (pinfunction "1_1") (pintype "passive"))
      (node (ref "C243") (pin "1") (pinfunction "1_1") (pintype "passive"))
      (node (ref "C244") (pin "1") (pinfunction "1_1") (pintype "passive"))
      (node (ref "C245") (pin "1") (pinfunction "1_1") (pintype "passive"))
      (node (ref "C246") (pin "1") (pinfunction "1_1") (pintype "passive"))
      (node (ref "C247") (pin "1") (pinfunction "1_1") (pintype "passive"))
      (node (ref "C248") (pin "1") (pinfunction "1_1") (pintype "passive"))
      (node (ref "C249") (pin "1") (pinfunction "1_1") (pintype "passive"))
      (node (ref "C250") (pin "1") (pinfunction "1_1") (pintype "passive"))
      (node (ref "C251") (pin "1") (pinfunction "1_1") (pintype "passive"))
      (node (ref "C252") (pin "1") (pinfunction "1_1") (pintype "passive"))
      (node (ref "C253") (pin "1") (pinfunction "1_1") (pintype "passive"))
      (node (ref "C254") (pin "1") (pinfunction "1_1") (pintype "passive"))
      (node (ref "C255") (pin "1") (pinfunction "1_1") (pintype "passive"))
      (node (ref "C256") (pin "1") (pinfunction "1_1") (pintype "passive"))
      (node (ref "C257") (pin "1") (pinfunction "1_1") (pintype "passive"))
      (node (ref "C258") (pin "1") (pinfunction "1_1") (pintype "passive"))
      (node (ref "C259") (pin "1") (pinfunction "1_1") (pintype "passive"))
      (node (ref "C260") (pin "1") (pinfunction "1_1") (pintype "passive"))
      (node (ref "C261") (pin "1") (pinfunction "1_1") (pintype "passive"))
      (node (ref "C262") (pin "1") (pinfunction "1_1") (pintype "passive"))
      (node (ref "C263") (pin "1") (pinfunction "1_1") (pintype "passive"))
      (node (ref "C264") (pin "1") (pinfunction "1_1") (pintype "passive"))
      (node (ref "C265") (pin "1") (pinfunction "1_1") (pintype "passive"))
      (node (ref "C266") (pin "1") (pinfunction "1_1") (pintype "passive"))
      (node (ref "R205") (pin "1") (pinfunction "1_1") (pintype "passive"))
      (node (ref "R207") (pin "2") (pinfunction "2_2") (pintype "passive"))
      (node (ref "R208") (pin "2") (pinfunction "2_2") (pintype "passive"))
      (node (ref "U200") (pin "A10") (pinfunction "DGND_A10") (pintype "passive"))
      (node (ref "U200") (pin "B3") (pinfunction "PLL2GND_B3") (pintype "passive"))
      (node (ref "U200") (pin "C1") (pinfunction "AGND_C1") (pintype "passive"))
      (node (ref "U200") (pin "C8") (pinfunction "DGND_C8") (pintype "passive"))
      (node (ref "U200") (pin "C9") (pinfunction "AGND_C9") (pintype "passive"))
      (node (ref "U200") (pin "D4") (pinfunction "DGND_D4") (pintype "passive"))
      (node (ref "U200") (pin "D7") (pinfunction "EGND_D7") (pintype "passive"))
      (node (ref "U200") (pin "E1") (pinfunction "DGND_E1") (pintype "passive"))
      (node (ref "U200") (pin "E2") (pinfunction "ASGND_E2") (pintype "passive"))
      (node (ref "U200") (pin "E3") (pinfunction "AGND_E3") (pintype "passive"))
      (node (ref "U200") (pin "E4") (pinfunction "DGND_E4") (pintype "passive"))
      (node (ref "U200") (pin "E5") (pinfunction "DGND_E5") (pintype "passive"))
      (node (ref "U200") (pin "E6") (pinfunction "DGND_E6") (pintype "passive"))
      (node (ref "U200") (pin "E7") (pinfunction "DGND_E7") (pintype "passive"))
      (node (ref "U200") (pin "E8") (pinfunction "DGND_E8") (pintype "passive"))
      (node (ref "U200") (pin "F3") (pinfunction "DGND_F3") (pintype "passive"))
      (node (ref "U200") (pin "F4") (pinfunction "DGND_F4") (pintype "passive"))
      (node (ref "U200") (pin "F5") (pinfunction "DGND_F5") (pintype "passive"))
      (node (ref "U200") (pin "F6") (pinfunction "DGND_F6") (pintype "passive"))
      (node (ref "U200") (pin "F7") (pinfunction "ASGND_F7") (pintype "passive"))
      (node (ref "U200") (pin "G1") (pinfunction "AGND_G1") (pintype "passive"))
      (node (ref "U200") (pin "G3") (pinfunction "DGND_G3") (pintype "passive"))
      (node (ref "U200") (pin "G4") (pinfunction "DGND_G4") (pintype "passive"))
      (node (ref "U200") (pin "G9") (pinfunction "AGND_G9") (pintype "passive"))
      (node (ref "U200") (pin "H3") (pinfunction "AGND_H3") (pintype "passive"))
      (node (ref "U200") (pin "J5") (pinfunction "ASGND_J5") (pintype "passive"))
      (node (ref "U200") (pin "J8") (pinfunction "AGND_J8") (pintype "passive"))
      (node (ref "U201") (pin "2") (pinfunction "GND_2") (pintype "power_in"))
      (node (ref "U202") (pin "2") (pinfunction "GND_2") (pintype "power_in"))
      (node (ref "U203") (pin "2") (pinfunction "GND_2") (pintype "power_in"))
      (node (ref "X200") (pin "2") (pinfunction "GND_2") (pintype "passive"))
    )
    (net (code "41") (name "Net-(U200-TM)") (class "Default")
      (node (ref "R207") (pin "1") (pinfunction "1_1") (pintype "passive"))
      (node (ref "U200") (pin "J9") (pinfunction "TM_J9") (pintype "passive"))
    )
    (net (code "42") (name "Net-(X200-OUT)") (class "Default")
      (node (ref "R206") (pin "1") (pinfunction "1_1") (pintype "passive"))
      (node (ref "X200") (pin "3") (pinfunction "OUT_3") (pintype "passive"))
    )
    (net (code "43") (name "unconnected-(U200-NC1-PadA1)") (class "Default")
      (node (ref "U200") (pin "A1") (pinfunction "NC1_A1") (pintype "passive"))
    )
    (net (code "44") (name "unconnected-(U200-NC2-PadJ1)") (class "Default")
      (node (ref "U200") (pin "J1") (pinfunction "NC2_J1") (pintype "passive"))
    )
    (net (code "45") (name "unconnected-(U200-NC3-PadJ10)") (class "Default")
      (node (ref "U200") (pin "J10") (pinfunction "NC3_J10") (pintype "passive"))
    )
    (net (code "46") (name "unconnected-(U200-PCLK-PadC4)") (class "Default")
      (node (ref "U200") (pin "C4") (pinfunction "PCLK_C4") (pintype "passive"))
    )
  )
)
